# CAN_FD_INTERFACE.net
KiCad netlist of a schematic drawn in Altium Designer
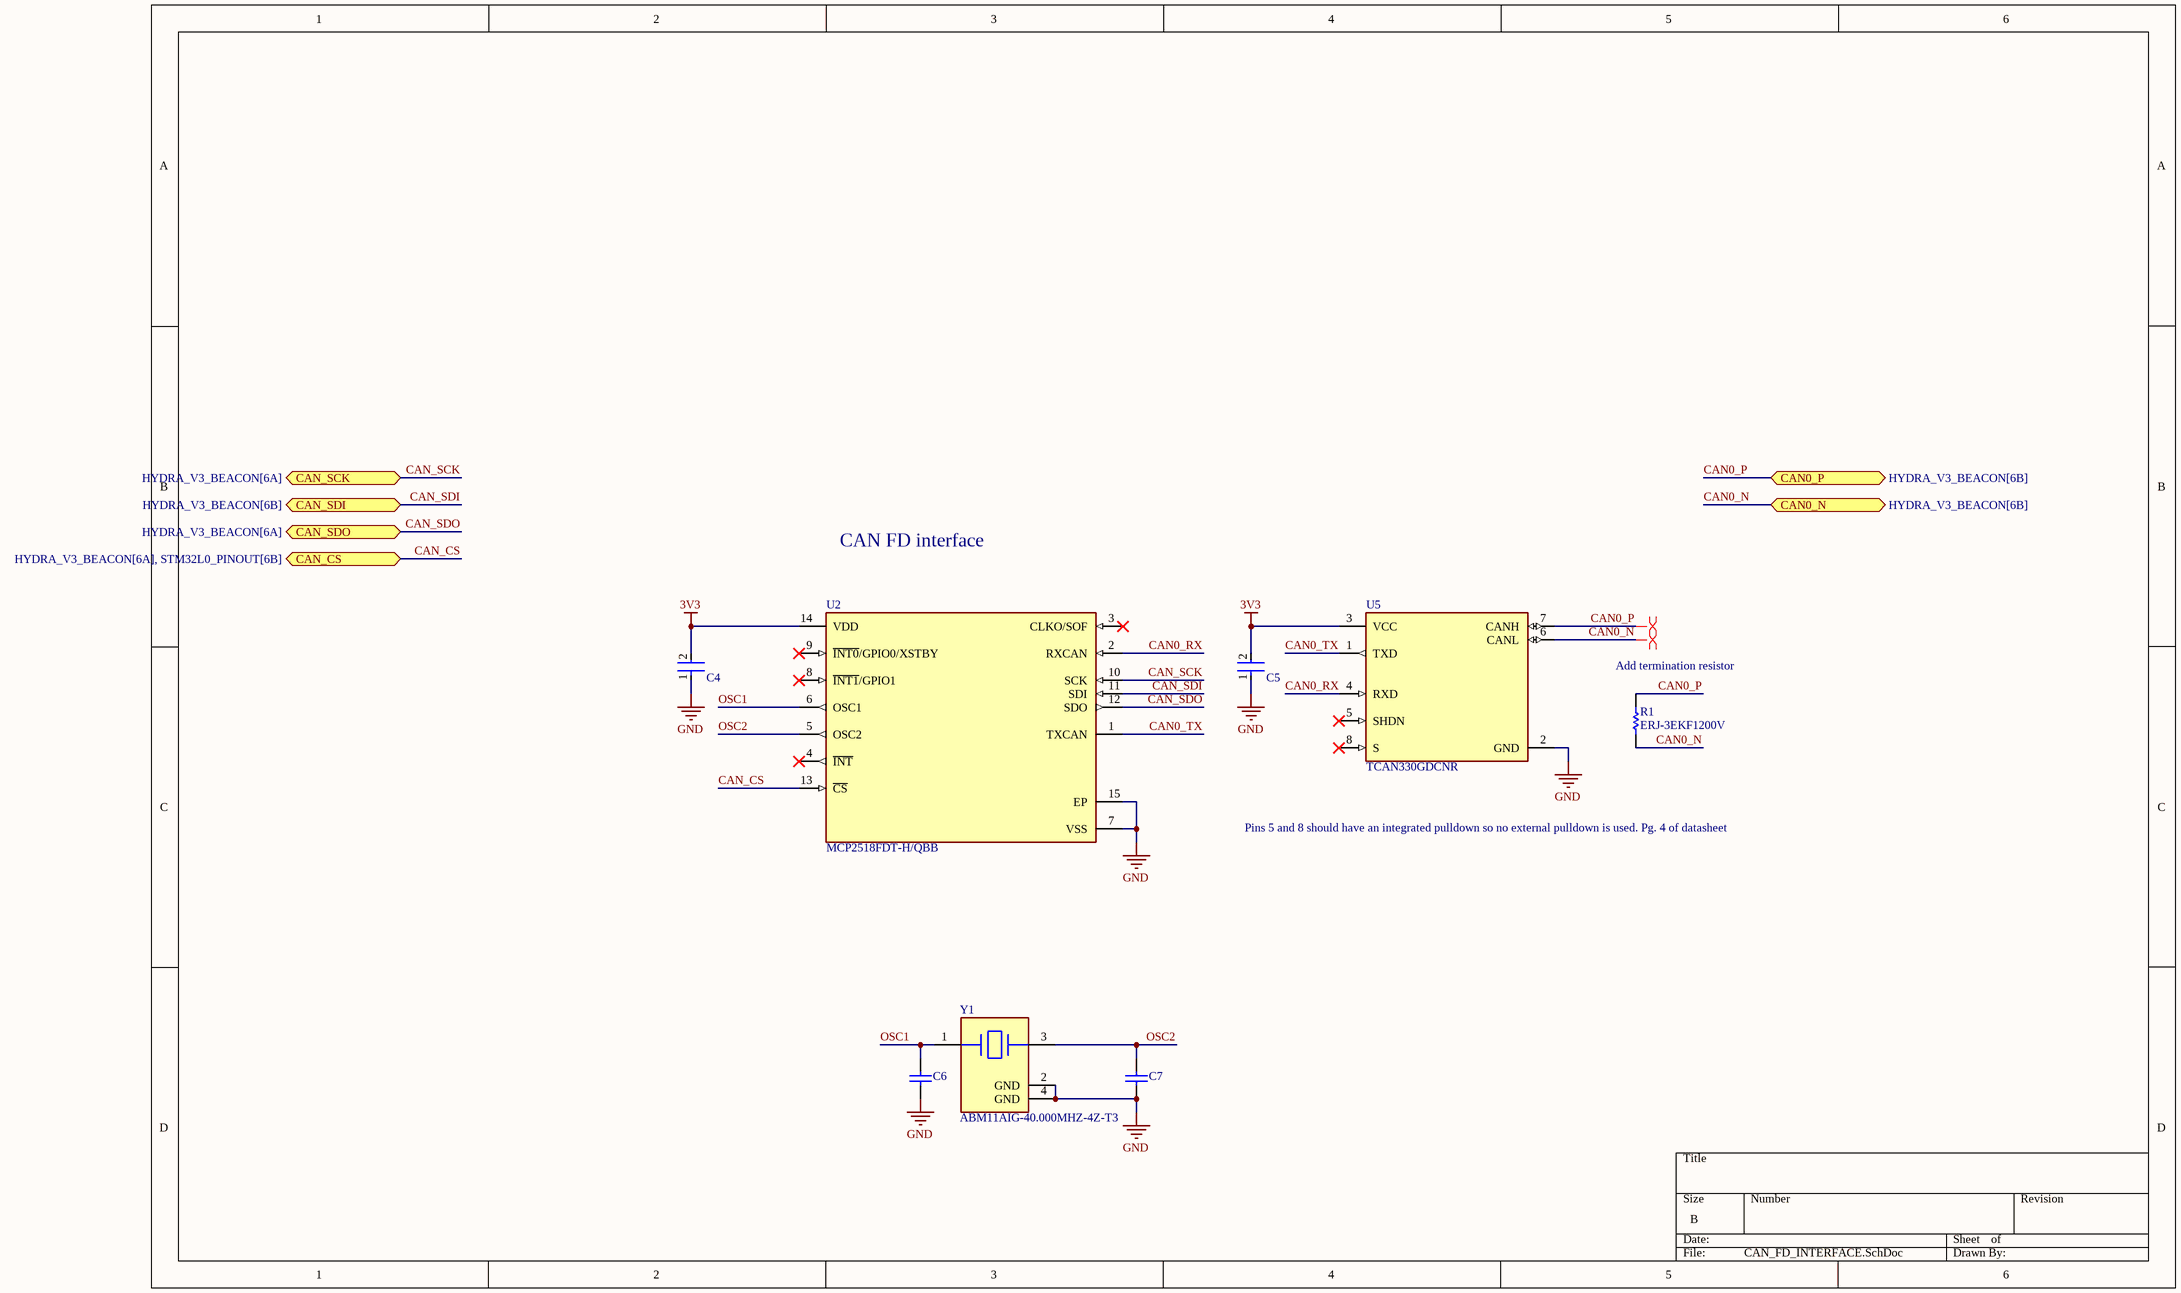
[diagram p0: CAN_FD_INTERFACE.SchDoc]

(export (version "E")
  (design (tool "Eeschema 10.0.6"))
  (components
    (comp (ref "C4")
      (value "C0402C104K8PACTU")
      (footprint "FP-C0402-BB-MFG")
      (description "CAP CER 0.1UF 10V X5R 0402")
      (fields (field (name "MANUFACTURER") "Kemet") (field (name "TOLERANCE") "0.1"))
      (libsource (lib "Altium Content Vault") (part "b4654b650e69147ec39a6b967a45e02"))
    )
    (comp (ref "C5")
      (value "C0402C104K8PACTU")
      (footprint "FP-C0402-BB-MFG")
      (description "CAP CER 0.1UF 10V X5R 0402")
      (fields (field (name "MANUFACTURER") "Kemet") (field (name "TOLERANCE") "0.1"))
      (libsource (lib "Altium Content Vault") (part "b4654b650e69147ec39a6b967a45e02"))
    )
    (comp (ref "C6")
      (value "VJ0603D6R8CXPAJ")
      (footprint "CAPC1608X92X38LL15T08")
      (fields (field (name "MANUFACTURER") "Vitramon"))
      (libsource (lib "Altium Content Vault") (part "CAP"))
    )
    (comp (ref "C7")
      (value "VJ0603D6R8CXPAJ")
      (footprint "CAPC1608X92X38LL15T08")
      (fields (field (name "MANUFACTURER") "Vitramon"))
      (libsource (lib "Altium Content Vault") (part "CAP"))
    )
    (comp (ref "R1")
      (value "ERJ-3EKF1200V")
      (footprint "RESC1609X55X30ML15T15")
      (description "Chip Resistor, 120 Ohm, +/- 1%, 0.1 W, -55 to 155 degC, 0603 (1608 Metric), RoHS, Tape and Reel")
      (fields (field (name "TOLERANCE") "1%") (field (name "MANUFACTURER") "Panasonic"))
      (libsource (lib "Altium Content Vault") (part "RES-2"))
    )
    (comp (ref "U2")
      (value "MCP2518FDT-H/QBB")
      (footprint "FP-C04-21361-MFG")
      (description "IC CAN CONTROLLER SPI 14VDFN")
      (libsource (lib "Altium Content Vault") (part "171200ff88dd600c7d3e4b98ff00d41"))
    )
    (comp (ref "U5")
      (value "TCAN330GDCNR")
      (footprint "FP-DCN0008A-MFG")
      (description "IC TRANSCEIVER 1/1 SOT23-8")
      (libsource (lib "Altium Content Vault") (part "22681b49c22ad38c6a4e12e04c36c7a"))
    )
    (comp (ref "Y1")
      (value "ABM11AIG-40.000MHZ-4Z-T3")
      (footprint "FP-ABM11AIG-MFG")
      (description "Crystal 40MHz ±30ppm 10pF SMD-4 2mm x 1.6mm Automotive")
      (libsource (lib "Altium Content Vault") (part "51b5329859b7ce12e0c2ce5858bdf70"))
    )
  )
  (nets
    (net (code "1") (name "/CAN0_N") (class "Default")
      (node (ref "R1") (pin "1") (pinfunction "1_1") (pintype "passive"))
      (node (ref "U5") (pin "6") (pinfunction "CANL_6") (pintype "bidirectional"))
    )
    (net (code "2") (name "/CAN0_P") (class "Default")
      (node (ref "R1") (pin "2") (pinfunction "2_2") (pintype "passive"))
      (node (ref "U5") (pin "7") (pinfunction "CANH_7") (pintype "bidirectional"))
    )
    (net (code "3") (name "/CAN0_RX") (class "Default")
      (node (ref "U2") (pin "2") (pinfunction "RXCAN_2") (pintype "input"))
      (node (ref "U5") (pin "4") (pinfunction "RXD_4") (pintype "input"))
    )
    (net (code "4") (name "/CAN0_TX") (class "Default")
      (node (ref "U2") (pin "1") (pinfunction "TXCAN_1") (pintype "passive"))
      (node (ref "U5") (pin "1") (pinfunction "TXD_1") (pintype "output"))
    )
    (net (code "5") (name "/CAN_CS") (class "Default")
      (node (ref "U2") (pin "13") (pinfunction "~{CS}_13") (pintype "input"))
    )
    (net (code "6") (name "/CAN_SCK") (class "Default")
      (node (ref "U2") (pin "10") (pinfunction "SCK_10") (pintype "input"))
    )
    (net (code "7") (name "/CAN_SDI") (class "Default")
      (node (ref "U2") (pin "11") (pinfunction "SDI_11") (pintype "input"))
    )
    (net (code "8") (name "/CAN_SDO") (class "Default")
      (node (ref "U2") (pin "12") (pinfunction "SDO_12") (pintype "output"))
    )
    (net (code "9") (name "/OSC1") (class "Default")
      (node (ref "C6") (pin "2") (pinfunction "2_2") (pintype "passive"))
      (node (ref "U2") (pin "6") (pinfunction "OSC1_6") (pintype "output"))
      (node (ref "Y1") (pin "1") (pinfunction "1_Crystal_1") (pintype "passive"))
    )
    (net (code "10") (name "/OSC2") (class "Default")
      (node (ref "C7") (pin "2") (pinfunction "2_2") (pintype "passive"))
      (node (ref "U2") (pin "5") (pinfunction "OSC2_5") (pintype "output"))
      (node (ref "Y1") (pin "3") (pinfunction "2_Crystal_3") (pintype "passive"))
    )
    (net (code "11") (name "3V3") (class "Default")
      (node (ref "C4") (pin "2") (pinfunction "2_2") (pintype "passive"))
      (node (ref "C5") (pin "2") (pinfunction "2_2") (pintype "passive"))
      (node (ref "U2") (pin "14") (pinfunction "VDD_14") (pintype "power_in"))
      (node (ref "U5") (pin "3") (pinfunction "VCC_3") (pintype "power_in"))
    )
    (net (code "12") (name "GND") (class "Default")
      (node (ref "C4") (pin "1") (pinfunction "1_1") (pintype "passive"))
      (node (ref "C5") (pin "1") (pinfunction "1_1") (pintype "passive"))
      (node (ref "C6") (pin "1") (pinfunction "1_1") (pintype "passive"))
      (node (ref "C7") (pin "1") (pinfunction "1_1") (pintype "passive"))
      (node (ref "U2") (pin "15") (pinfunction "EP_15") (pintype "power_in"))
      (node (ref "U2") (pin "7") (pinfunction "VSS_7") (pintype "power_in"))
      (node (ref "U5") (pin "2") (pinfunction "GND_2") (pintype "power_in"))
      (node (ref "Y1") (pin "2") (pinfunction "GND_2") (pintype "power_in"))
      (node (ref "Y1") (pin "4") (pinfunction "GND_4") (pintype "power_in"))
    )
    (net (code "13") (name "unconnected-(U2-CLKO{slash}SOF-Pad3)") (class "Default")
      (node (ref "U2") (pin "3") (pinfunction "CLKO/SOF_3") (pintype "input+no_connect"))
    )
    (net (code "14") (name "unconnected-(U2-~{INT0}{slash}GPIO0{slash}XSTBY-Pad9)") (class "Default")
      (node (ref "U2") (pin "9") (pinfunction "~{INT0}/GPIO0/XSTBY_9") (pintype "input+no_connect"))
    )
    (net (code "15") (name "unconnected-(U2-~{INT1}{slash}GPIO1-Pad8)") (class "Default")
      (node (ref "U2") (pin "8") (pinfunction "~{INT1}/GPIO1_8") (pintype "input+no_connect"))
    )
    (net (code "16") (name "unconnected-(U2-~{INT}-Pad4)") (class "Default")
      (node (ref "U2") (pin "4") (pinfunction "~{INT}_4") (pintype "output+no_connect"))
    )
    (net (code "17") (name "unconnected-(U5-S-Pad8)") (class "Default")
      (node (ref "U5") (pin "8") (pinfunction "S_8") (pintype "input+no_connect"))
    )
    (net (code "18") (name "unconnected-(U5-SHDN-Pad5)") (class "Default")
      (node (ref "U5") (pin "5") (pinfunction "SHDN_5") (pintype "input+no_connect"))
    )
  )
)
